# Pump.net
KiCad netlist of a schematic drawn in Altium Designer
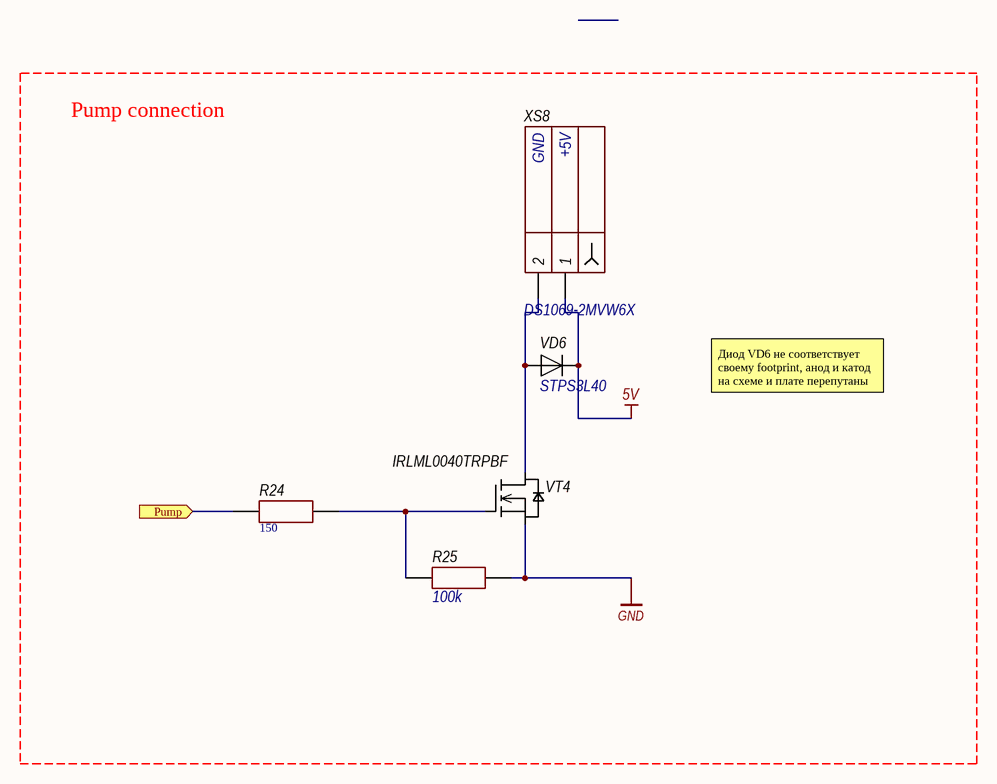
[diagram p0: Pump.SchDoc]

(export (version "E")
  (design (tool "Eeschema 10.0.6"))
  (components
    (comp (ref "R24")
      (value "RC0603FR-07150RL")
      (footprint "RESC0603_N")
      (description "RES SMD 150 OHM 1% 1/10W 0603")
      (fields
        (field (name "MANUFACTURER") "Yageo")
        (field (name "RESISTANCE") "150")
        (field (name "TOLERANCE") "1%")
        (field (name "AUTHOR") "M.S. Koval")
      )
      (libsource (lib "") (part "R_GENERAL_1"))
    )
    (comp (ref "R25")
      (value "RC0603FR-07100KL")
      (footprint "RESC0603_N")
      (description "RES SMD 100 KOHM 1% 1/10W 0603")
      (fields
        (field (name "MANUFACTURER") "Yageo")
        (field (name "RESISTANCE") "100k")
        (field (name "TOLERANCE") "1%")
        (field (name "AUTHOR") "M.S. Koval")
      )
      (libsource (lib "EnCata Concord Pro") (part "R_GENERAL"))
    )
    (comp (ref "VD6")
      (value "STPS3L40")
      (footprint "STPS3L40")
      (description "Rectifier Diode, Schottky, 1 Phase, 1 Element, 3A, 40V V(RRM), Silicon, DO-214AB")
      (fields (field (name "MANUFACTURER") "ST") (field (name "AUTHOR") "v.taranov"))
      (libsource (lib "EnCata Concord Pro") (part "Diode"))
    )
    (comp (ref "VT4")
      (value "IRLML0040TRPBF")
      (footprint "SOT-23-3")
      (description "40V 3.6A 56mΩ@10V,3.6A 1.3W N Channel SOT-23 MOSFETs ROHS")
      (fields
        (field (name "MANUFACTURER") "Infineon Technologies")
        (field (name "MANUFACTURER PART NUMBER") "IRLML0040TRPbF")
        (field (name "AUTHOR") "m.boltromeyuk")
      )
      (libsource (lib "EnCata Concord Pro") (part "MOSFET N-ch (1G-2S-3D)"))
    )
    (comp (ref "XS8")
      (value "DS1069-2MVW6X")
      (footprint "CWF-2")
      (description "2.5mm, 2 pin, Male, 3A, Vertical mounting, CONNFLY")
      (fields
        (field (name "NET2") "GND")
        (field (name "NET1") "+5V")
        (field (name "MANUFACTURER") "CONNFLY")
        (field (name "AUTHOR") "a.antipov")
      )
      (libsource (lib "EnCata Concord Pro") (part "XS2"))
    )
  )
  (nets
    (net (code "1") (name "/Pump") (class "Default")
      (node (ref "R24") (pin "1") (pinfunction "1_1") (pintype "passive"))
    )
    (net (code "2") (name "5V") (class "Default")
      (node (ref "VD6") (pin "2") (pinfunction "2_2") (pintype "passive"))
      (node (ref "XS8") (pin "1") (pinfunction "1_1") (pintype "passive"))
    )
    (net (code "3") (name "GND") (class "Default")
      (node (ref "R25") (pin "1") (pinfunction "1_1") (pintype "passive"))
      (node (ref "VT4") (pin "2") (pinfunction "S_2") (pintype "passive"))
    )
    (net (code "4") (name "Net-(VT4-D)") (class "Default")
      (node (ref "VD6") (pin "1") (pinfunction "1_1") (pintype "passive"))
      (node (ref "VT4") (pin "3") (pinfunction "D_3") (pintype "passive"))
      (node (ref "XS8") (pin "2") (pinfunction "2_2") (pintype "passive"))
    )
    (net (code "5") (name "Net-(VT4-G)") (class "Default")
      (node (ref "R24") (pin "2") (pinfunction "2_2") (pintype "passive"))
      (node (ref "R25") (pin "2") (pinfunction "2_2") (pintype "passive"))
      (node (ref "VT4") (pin "1") (pinfunction "G_1") (pintype "passive"))
    )
  )
)
